# Power.net
KiCad netlist of a schematic drawn in Altium Designer
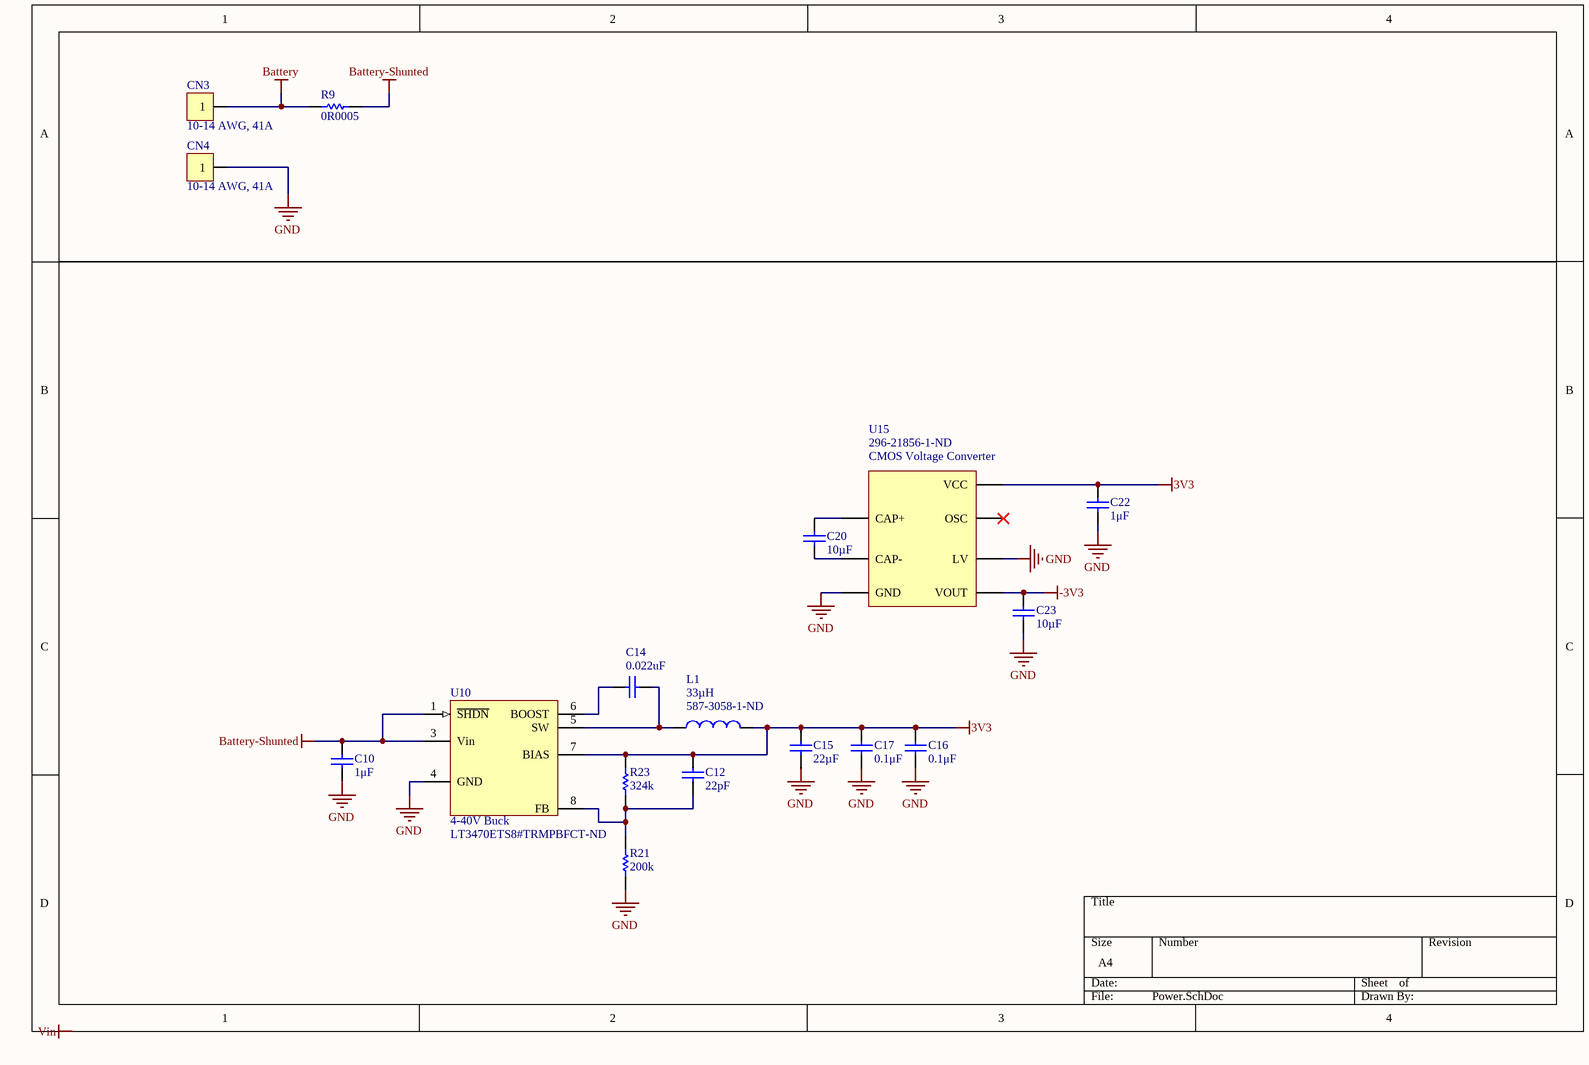
[diagram p0: Power.SchDoc]

(export (version "E")
  (design (tool "Eeschema 10.0.6"))
  (components
    (comp (ref "C10")
      (value "1μF")
      (footprint "CAPC1608N(0603\")")
      (description "Capacitor, Ceramic, 25V, +/- 10%, 0603 SMD, X5R")
      (fields
        (field (name "MFG") "Murata-Electronics-North-America")
        (field (name "PUBLISHER") "AUVic")
        (field (name "CREATED BY") "Andy Bates")
      )
      (libsource (lib "AUVic_Integrated_Library_Capacitors") (part "1uF 25V 0603 SMD, Ceramic"))
    )
    (comp (ref "C12")
      (value "22pF")
      (footprint "CAPC1608N(0603\")")
      (description "Capacitor, Ceramic, 50V, +/-5%, 0603 SMD, X7R")
      (fields (field (name "CREATED BY") "Andy Bates"))
      (libsource (lib "AUVic_Integrated_Library_Capacitors") (part "22pF 50V 0603 SMD, Ceramic"))
    )
    (comp (ref "C14")
      (value "0.022uF")
      (footprint "CAPC1608N(0603\")")
      (description "Capacitor, Ceramic, 50V, +/-10%, 0603 SMD, X7R")
      (fields (field (name "CREATED BY") "Andy Bates"))
      (libsource (lib "AUVic_Integrated_Library_Capacitors") (part "0.022uF 50V 0603 SMD, Ceramic"))
    )
    (comp (ref "C15")
      (value "22µF")
      (footprint "CAPC2012N(0805\")")
      (description "Capacitor, Ceramic, 35V, +/- 20%, 0805 SMD, X5R")
      (fields (field (name "PUBLISHER") "AUVic"))
      (libsource (lib "AUVic_Integrated_Library_Capacitors") (part "22uF 35V 0805 SMD, Ceramic"))
    )
    (comp (ref "C16")
      (value "0.1μF")
      (footprint "CAPC1608N(0603\")")
      (description "Capacitor, Ceramic, 100V, +/- 10%, 0603 SMD, X7R")
      (fields
        (field (name "MFG") "TDK")
        (field (name "PUBLISHER") "AUVic")
        (field (name "CREATED BY") "Ashwin Sira")
      )
      (libsource (lib "AUVic_Integrated_Library_Capacitors") (part "0.1uF 100V 0603 SMD, Ceramic"))
    )
    (comp (ref "C17")
      (value "0.1μF")
      (footprint "CAPC1608N(0603\")")
      (description "Capacitor, Ceramic, 100V, +/- 10%, 0603 SMD, X7R")
      (fields
        (field (name "MFG") "TDK")
        (field (name "PUBLISHER") "AUVic")
        (field (name "CREATED BY") "Ashwin Sira")
      )
      (libsource (lib "AUVic_Integrated_Library_Capacitors") (part "0.1uF 100V 0603 SMD, Ceramic"))
    )
    (comp (ref "C20")
      (value "10µF")
      (footprint "CAPC2012N(0805\")")
      (description "Capacitor, Ceramic, 10V, +/- 10%, 0805 SMD, X5R")
      (fields (field (name "PUBLISHER") "AUVic") (field (name "MADE BY") "Andy Bates"))
      (libsource (lib "AUVic_Integrated_Library_Capacitors") (part "10uF 10V 0805 SMD, Ceramic"))
    )
    (comp (ref "C22")
      (value "1μF")
      (footprint "CAPC1608N(0603\")")
      (description "Capacitor, Ceramic, 25V, +/- 10%, 0603 SMD, X5R")
      (fields
        (field (name "MFG") "Murata-Electronics-North-America")
        (field (name "PUBLISHER") "AUVic")
        (field (name "CREATED BY") "Andy Bates")
      )
      (libsource (lib "AUVic_Integrated_Library_Capacitors") (part "1uF 25V 0603 SMD, Ceramic"))
    )
    (comp (ref "C23")
      (value "10µF")
      (footprint "CAPC2012N(0805\")")
      (description "Capacitor, Ceramic, 10V, +/- 10%, 0805 SMD, X5R")
      (fields (field (name "PUBLISHER") "AUVic") (field (name "MADE BY") "Andy Bates"))
      (libsource (lib "AUVic_Integrated_Library_Capacitors") (part "10uF 10V 0805 SMD, Ceramic"))
    )
    (comp (ref "CN3")
      (value "10-14 AWG, 41A")
      (footprint "1x1, Phoenix Contact 1704837,THT")
      (description "1x1, Phoenix Contact 1704837,THT")
      (fields (field (name "PUBLISHER") "Andy Bates") (field (name "REVIEWED BY") "*"))
      (libsource (lib "AUVic_Integrated_Library_Connectors") (part "1x1, Phoenix Contact 1704837,THT"))
    )
    (comp (ref "CN4")
      (value "10-14 AWG, 41A")
      (footprint "1x1, Phoenix Contact 1704837,THT")
      (description "1x1, Phoenix Contact 1704837,THT")
      (fields (field (name "PUBLISHER") "Andy Bates") (field (name "REVIEWED BY") "*"))
      (libsource (lib "AUVic_Integrated_Library_Connectors") (part "1x1, Phoenix Contact 1704837,THT"))
    )
    (comp (ref "L1")
      (value "33µH")
      (footprint "CB - 1007 (2518)")
      (description "33µH 270mA 1.95Ohm")
      (fields
        (field (name "SUPPLIER PART NUMBER 1") "587-3058-1-ND")
        (field (name "CREATED BY") "Andy Bates")
      )
      (libsource (lib "AUVic_Integrated_Library_Inductors") (part "33µH 270mA 1.95Ohm"))
    )
    (comp (ref "R9")
      (value "0R0005")
      (footprint "RESC6332N(2512\")")
      (description "0R0005, 1%, 3W, 2512 SMD")
      (fields
        (field (name "MFG") "Riedon")
        (field (name "CREATED BY") "Ashwin Sira")
        (field (name "PUBLISHER") "AUVic")
      )
      (libsource (lib "AUVic_Integrated_Library_Resistors") (part "0R0005, 1%, 3W, 2512 SMD"))
    )
    (comp (ref "R21")
      (value "200k")
      (footprint "RESC1608N(0603\")")
      (description "200kR, 1%, 1/10W, 0603 SMD")
      (fields (field (name "MADE BY") "Ashwin Sira"))
      (libsource (lib "AUVic_Integrated_Library_Resistors") (part "200kR, 1%, 1/10W, 0603 SMD"))
    )
    (comp (ref "R23")
      (value "324k")
      (footprint "RESC1608N(0603\")")
      (description "324kR, 1%, 1/10W, 0603 SMD")
      (fields (field (name "MADE BY") "Andy Bates"))
      (libsource (lib "AUVic_Integrated_Library_Resistors") (part "324kR, 1%, 1/10W, 0603 SMD"))
    )
    (comp (ref "U10")
      (value "4-40V Buck")
      (footprint "TSOT-23-8")
      (description "Low Noise Step-Down Switching Regulator, 123-8-pin TSOT, 0 to 85 degC")
      (fields
        (field (name "MANUFACTURER") "Linear Technology")
        (field (name "SUPPLIER PART NUMBER 1") "LT3470ETS8#TRMPBFCT-ND")
      )
      (libsource (lib "AUVic_Integrated_Library_Regulators") (part "LT3470ETS8#TRMPBF"))
    )
    (comp (ref "U15")
      (value "CMOS Voltage Converter")
      (footprint "8-SOIC")
      (fields
        (field (name "MANUFACTURER PART NO.") "TL7660")
        (field (name "SUPPLIER PART NUMBER 1") "296-21856-1-ND")
        (field (name "PUBLISHER") "Altium Limited")
        (field (name "CREATED BY") "Jordan")
      )
      (libsource (lib "AUVic_Integrated_Library_Regulators") (part "TL7660"))
    )
  )
  (nets
    (net (code "1") (name "-3V3") (class "Default")
      (node (ref "C23") (pin "2") (pinfunction "Cathode_2") (pintype "passive"))
      (node (ref "U15") (pin "5") (pinfunction "VOUT_5") (pintype "passive"))
    )
    (net (code "2") (name "3V3") (class "Default")
      (node (ref "C12") (pin "1") (pinfunction "1_1") (pintype "passive"))
      (node (ref "C15") (pin "2") (pinfunction "Cathode_2") (pintype "passive"))
      (node (ref "C16") (pin "1") (pinfunction "Anode_1") (pintype "passive"))
      (node (ref "C17") (pin "1") (pinfunction "Anode_1") (pintype "passive"))
      (node (ref "C22") (pin "2") (pinfunction "Cathode_2") (pintype "passive"))
      (node (ref "L1") (pin "2") (pinfunction "2_2") (pintype "passive"))
      (node (ref "R23") (pin "2") (pinfunction "2_2") (pintype "passive"))
      (node (ref "U10") (pin "7") (pinfunction "BIAS_7") (pintype "passive"))
      (node (ref "U15") (pin "8") (pinfunction "VCC_8") (pintype "passive"))
    )
    (net (code "3") (name "Battery") (class "Default")
      (node (ref "CN3") (pin "1") (pinfunction "1_1") (pintype "passive"))
      (node (ref "R9") (pin "1") (pinfunction "1_1") (pintype "passive"))
    )
    (net (code "4") (name "Battery-Shunted") (class "Default")
      (node (ref "C10") (pin "2") (pinfunction "Cathode_2") (pintype "passive"))
      (node (ref "R9") (pin "2") (pinfunction "2_2") (pintype "passive"))
      (node (ref "U10") (pin "1") (pinfunction "~{SHDN}_1") (pintype "input"))
      (node (ref "U10") (pin "3") (pinfunction "Vin_3") (pintype "power_in"))
    )
    (net (code "5") (name "GND") (class "Default")
      (node (ref "C10") (pin "1") (pinfunction "Anode_1") (pintype "passive"))
      (node (ref "C15") (pin "1") (pinfunction "Anode_1") (pintype "passive"))
      (node (ref "C16") (pin "2") (pinfunction "Cathode_2") (pintype "passive"))
      (node (ref "C17") (pin "2") (pinfunction "Cathode_2") (pintype "passive"))
      (node (ref "C22") (pin "1") (pinfunction "Anode_1") (pintype "passive"))
      (node (ref "C23") (pin "1") (pinfunction "Anode_1") (pintype "passive"))
      (node (ref "CN4") (pin "1") (pinfunction "1_1") (pintype "passive"))
      (node (ref "R21") (pin "1") (pinfunction "1_1") (pintype "passive"))
      (node (ref "U10") (pin "4") (pinfunction "GND_4") (pintype "power_in"))
      (node (ref "U15") (pin "3") (pinfunction "GND_3") (pintype "passive"))
      (node (ref "U15") (pin "6") (pinfunction "LV_6") (pintype "passive"))
    )
    (net (code "6") (name "Net-(C20-Anode)") (class "Default")
      (node (ref "C20") (pin "1") (pinfunction "Anode_1") (pintype "passive"))
      (node (ref "U15") (pin "4") (pinfunction "CAP-_4") (pintype "passive"))
    )
    (net (code "7") (name "Net-(C20-Cathode)") (class "Default")
      (node (ref "C20") (pin "2") (pinfunction "Cathode_2") (pintype "passive"))
      (node (ref "U15") (pin "2") (pinfunction "CAP+_2") (pintype "passive"))
    )
    (net (code "8") (name "Net-(U10-BOOST)") (class "Default")
      (node (ref "C14") (pin "1") (pinfunction "1_1") (pintype "passive"))
      (node (ref "U10") (pin "6") (pinfunction "BOOST_6") (pintype "passive"))
    )
    (net (code "9") (name "Net-(U10-FB)") (class "Default")
      (node (ref "C12") (pin "2") (pinfunction "2_2") (pintype "passive"))
      (node (ref "R21") (pin "2") (pinfunction "2_2") (pintype "passive"))
      (node (ref "R23") (pin "1") (pinfunction "1_1") (pintype "passive"))
      (node (ref "U10") (pin "8") (pinfunction "FB_8") (pintype "passive"))
    )
    (net (code "10") (name "Net-(U10-SW)") (class "Default")
      (node (ref "C14") (pin "2") (pinfunction "2_2") (pintype "passive"))
      (node (ref "L1") (pin "1") (pinfunction "1_1") (pintype "passive"))
      (node (ref "U10") (pin "5") (pinfunction "SW_5") (pintype "passive"))
    )
    (net (code "12") (name "unconnected-(U15-OSC-Pad7)") (class "Default")
      (node (ref "U15") (pin "7") (pinfunction "OSC_7") (pintype "passive+no_connect"))
    )
  )
)
